# RPX_Regulator_5V.net
KiCad netlist of a schematic drawn in Altium Designer
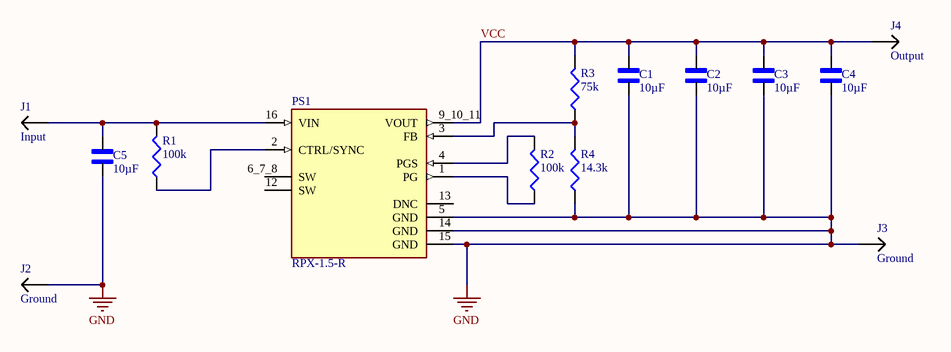
[diagram p0: RPX_Regulator_5V.SchDoc]

(export (version "E")
  (design (tool "Eeschema 10.0.6"))
  (components
    (comp (ref "C1")
      (value "10µF")
      (footprint "CAPC1608X90N")
      (description "0.47µF ±10% 50V Ceramic Capacitor X7R 0603 _1608 Metric_")
      (fields (field (name "MF") "TDK") (field (name "MP") "C1608X7R1H474K080AC"))
      (libsource (lib "lib") (part "C1608X7R1H474K080AC"))
    )
    (comp (ref "C2")
      (value "10µF")
      (footprint "CAPC1608X90N")
      (description "0.47µF ±10% 50V Ceramic Capacitor X7R 0603 _1608 Metric_")
      (fields (field (name "MF") "TDK") (field (name "MP") "C1608X7R1H474K080AC"))
      (libsource (lib "lib") (part "C1608X7R1H474K080AC"))
    )
    (comp (ref "C3")
      (value "10µF")
      (footprint "CAPC1608X90N")
      (description "0.47µF ±10% 50V Ceramic Capacitor X7R 0603 _1608 Metric_")
      (fields (field (name "MF") "TDK") (field (name "MP") "C1608X7R1H474K080AC"))
      (libsource (lib "lib") (part "C1608X7R1H474K080AC"))
    )
    (comp (ref "C4")
      (value "10µF")
      (footprint "CAPC1608X90N")
      (description "0.47µF ±10% 50V Ceramic Capacitor X7R 0603 _1608 Metric_")
      (fields (field (name "MF") "TDK") (field (name "MP") "C1608X7R1H474K080AC"))
      (libsource (lib "lib") (part "C1608X7R1H474K080AC"))
    )
    (comp (ref "C5")
      (value "10µF")
      (footprint "CAPC1608X90N")
      (description "0.47µF ±10% 50V Ceramic Capacitor X7R 0603 _1608 Metric_")
      (fields (field (name "MF") "TDK") (field (name "MP") "C1608X7R1H474K080AC"))
      (libsource (lib "lib") (part "C1608X7R1H474K080AC"))
    )
    (comp (ref "J1")
      (value "Input")
      (footprint "PAD")
      (description "Header 1")
      (fields (field (name "MF") "Connfly electronic (Zhenqin)") (field (name "MP") "PLS-3 (DS1021-1x3)"))
      (libsource (lib "lib") (part "PAD"))
    )
    (comp (ref "J2")
      (value "Ground")
      (footprint "PAD")
      (description "Header 1")
      (fields (field (name "MF") "Connfly electronic (Zhenqin)") (field (name "MP") "PLS-3 (DS1021-1x3)"))
      (libsource (lib "lib") (part "PAD"))
    )
    (comp (ref "J3")
      (value "Ground")
      (footprint "PAD")
      (description "Header 1")
      (fields (field (name "MF") "Connfly electronic (Zhenqin)") (field (name "MP") "PLS-3 (DS1021-1x3)"))
      (libsource (lib "lib") (part "PAD"))
    )
    (comp (ref "J4")
      (value "Output")
      (footprint "PAD")
      (description "Header 1")
      (fields (field (name "MF") "Connfly electronic (Zhenqin)") (field (name "MP") "PLS-3 (DS1021-1x3)"))
      (libsource (lib "lib") (part "PAD"))
    )
    (comp (ref "PS1")
      (value "RPX-1.5-R")
      (footprint "RPX-1.5-R:CONV_RPX-1.5-R")
      (fields (field (name "MF") "{'manufacturer': u'Recom Power'}"))
      (libsource (lib "*") (part "RPX-1.5-R"))
    )
    (comp (ref "R1")
      (value "100k")
      (footprint "J1-0603")
      (description "10 kOhms 1 0.1 W 1 10 W Chip Resistor 0603 1608 Metric Thick Film")
      (fields (field (name "MF") "Yageo or NXP") (field (name "MP") "10K 1% 0603"))
      (libsource (lib "lib") (part "RC0603FR-0710KL"))
    )
    (comp (ref "R2")
      (value "100k")
      (footprint "J1-0603")
      (description "10 kOhms 1 0.1 W 1 10 W Chip Resistor 0603 1608 Metric Thick Film")
      (fields (field (name "MF") "Yageo or NXP") (field (name "MP") "10K 1% 0603"))
      (libsource (lib "lib") (part "RC0603FR-0710KL"))
    )
    (comp (ref "R3")
      (value "75k")
      (footprint "J1-0603")
      (description "10 kOhms 1 0.1 W 1 10 W Chip Resistor 0603 1608 Metric Thick Film")
      (fields (field (name "MF") "Yageo or NXP") (field (name "MP") "10K 1% 0603"))
      (libsource (lib "lib") (part "RC0603FR-0710KL"))
    )
    (comp (ref "R4")
      (value "14.3k")
      (footprint "J1-0603")
      (description "10 kOhms 1 0.1 W 1 10 W Chip Resistor 0603 1608 Metric Thick Film")
      (fields (field (name "MF") "Yageo or NXP") (field (name "MP") "10K 1% 0603"))
      (libsource (lib "lib") (part "RC0603FR-0710KL"))
    )
  )
  (nets
    (net (code "1") (name "/VCC") (class "Default")
      (node (ref "C1") (pin "2") (pinfunction "2_2") (pintype "passive"))
      (node (ref "C2") (pin "2") (pinfunction "2_2") (pintype "passive"))
      (node (ref "C3") (pin "2") (pinfunction "2_2") (pintype "passive"))
      (node (ref "C4") (pin "2") (pinfunction "2_2") (pintype "passive"))
      (node (ref "J4") (pin "1") (pinfunction "1_1") (pintype "passive"))
      (node (ref "PS1") (pin "9_10_11") (pinfunction "VOUT_9_10_11") (pintype "output"))
      (node (ref "R3") (pin "2") (pinfunction "2_2") (pintype "passive"))
    )
    (net (code "2") (name "GND") (class "Default")
      (node (ref "C1") (pin "1") (pinfunction "1_1") (pintype "passive"))
      (node (ref "C2") (pin "1") (pinfunction "1_1") (pintype "passive"))
      (node (ref "C3") (pin "1") (pinfunction "1_1") (pintype "passive"))
      (node (ref "C4") (pin "1") (pinfunction "1_1") (pintype "passive"))
      (node (ref "C5") (pin "1") (pinfunction "1_1") (pintype "passive"))
      (node (ref "J2") (pin "1") (pinfunction "1_1") (pintype "passive"))
      (node (ref "J3") (pin "1") (pinfunction "1_1") (pintype "passive"))
      (node (ref "PS1") (pin "14") (pinfunction "GND_14") (pintype "power_in"))
      (node (ref "PS1") (pin "15") (pinfunction "GND_15") (pintype "power_in"))
      (node (ref "PS1") (pin "5") (pinfunction "GND_5") (pintype "power_in"))
      (node (ref "R4") (pin "1") (pinfunction "1_1") (pintype "passive"))
    )
    (net (code "3") (name "Net-(PS1-CTRL{slash}SYNC)") (class "Default")
      (node (ref "PS1") (pin "2") (pinfunction "CTRL/SYNC_2") (pintype "input"))
      (node (ref "R1") (pin "1") (pinfunction "1_1") (pintype "passive"))
    )
    (net (code "4") (name "Net-(PS1-FB)") (class "Default")
      (node (ref "PS1") (pin "3") (pinfunction "FB_3") (pintype "input"))
      (node (ref "R3") (pin "1") (pinfunction "1_1") (pintype "passive"))
      (node (ref "R4") (pin "2") (pinfunction "2_2") (pintype "passive"))
    )
    (net (code "5") (name "Net-(PS1-PG)") (class "Default")
      (node (ref "PS1") (pin "1") (pinfunction "PG_1") (pintype "output"))
      (node (ref "R2") (pin "1") (pinfunction "1_1") (pintype "passive"))
    )
    (net (code "6") (name "Net-(PS1-PGS)") (class "Default")
      (node (ref "PS1") (pin "4") (pinfunction "PGS_4") (pintype "input"))
      (node (ref "R2") (pin "2") (pinfunction "2_2") (pintype "passive"))
    )
    (net (code "7") (name "Net-(PS1-VIN)") (class "Default")
      (node (ref "C5") (pin "2") (pinfunction "2_2") (pintype "passive"))
      (node (ref "J1") (pin "1") (pinfunction "1_1") (pintype "passive"))
      (node (ref "PS1") (pin "16") (pinfunction "VIN_16") (pintype "input"))
      (node (ref "R1") (pin "2") (pinfunction "2_2") (pintype "passive"))
    )
    (net (code "8") (name "unconnected-(PS1-DNC-Pad13)") (class "Default")
      (node (ref "PS1") (pin "13") (pinfunction "DNC_13") (pintype "passive"))
    )
    (net (code "9") (name "unconnected-(PS1-SW-Pad6_7_8)") (class "Default")
      (node (ref "PS1") (pin "6_7_8") (pinfunction "SW_6_7_8") (pintype "passive"))
    )
    (net (code "10") (name "unconnected-(PS1-SW-Pad12)") (class "Default")
      (node (ref "PS1") (pin "12") (pinfunction "SW_12") (pintype "passive"))
    )
  )
)
